# TramHanSTM8.net
KiCad netlist of a schematic drawn in Altium Designer
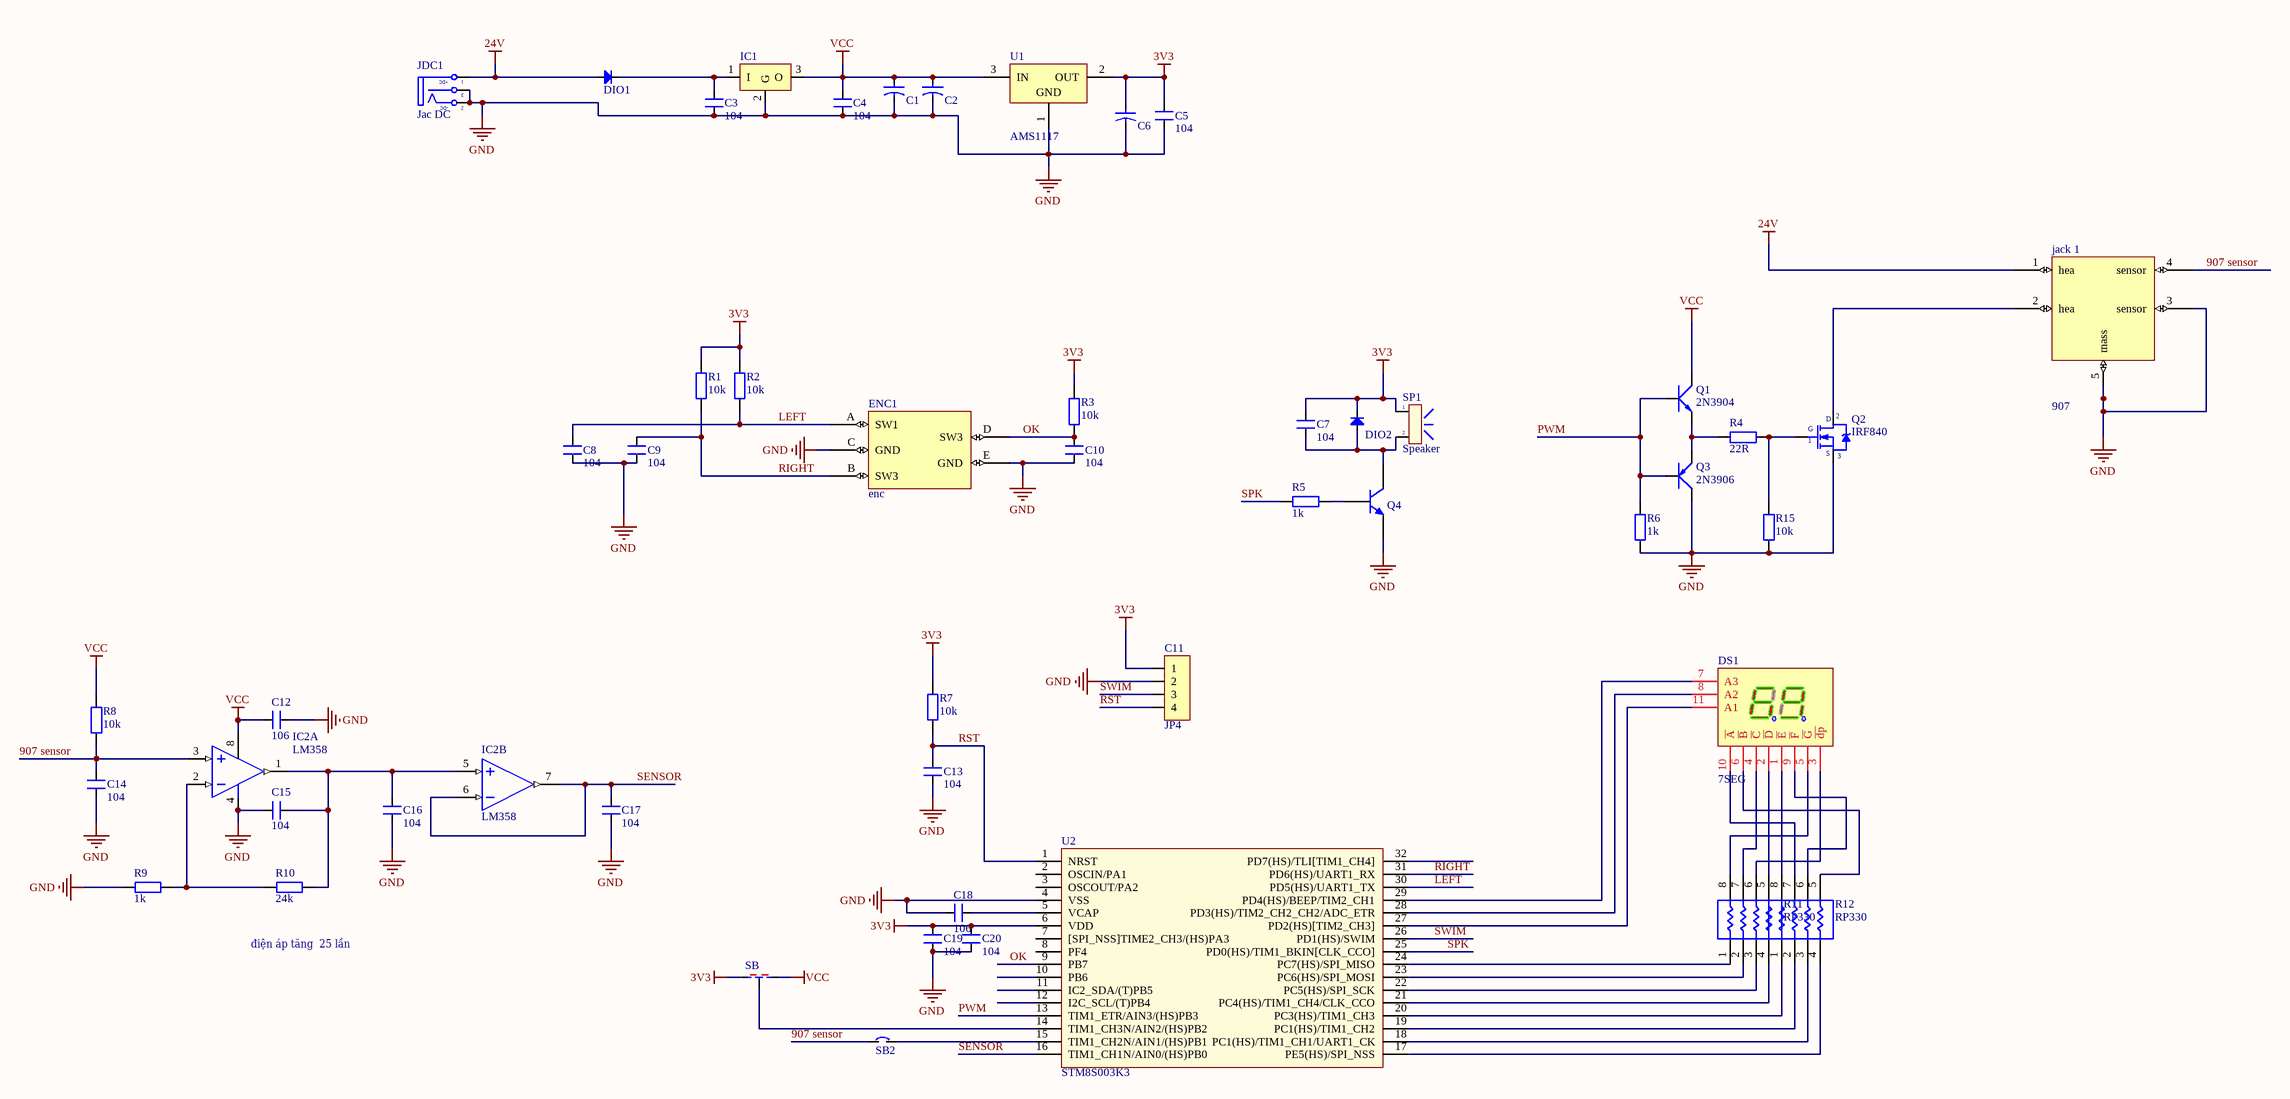
[diagram p0: TramHanSTM8.SchDoc]

(export (version "E")
  (design (tool "Eeschema 10.0.6"))
  (components
    (comp (ref "C1")
      (value "CAP")
      (footprint "C 1206")
      (libsource (lib "AltiumLibraryTieuBao (1)") (part "CAP"))
    )
    (comp (ref "C2")
      (value "CAP")
      (footprint "C 1206")
      (libsource (lib "AltiumLibraryTieuBao (1)") (part "CAP"))
    )
    (comp (ref "C3")
      (value "104")
      (footprint "SM-0805")
      (description "Cap SMD")
      (libsource (lib "Tesla_Thinh") (part "CM"))
    )
    (comp (ref "C4")
      (value "104")
      (footprint "SM-0805")
      (description "Cap SMD")
      (libsource (lib "Tesla_Thinh") (part "CM"))
    )
    (comp (ref "C5")
      (value "104")
      (footprint "SM-0805")
      (description "Cap SMD")
      (libsource (lib "Tesla_Thinh") (part "CM"))
    )
    (comp (ref "C6")
      (value "CAP")
      (footprint "C 1206")
      (libsource (lib "AltiumLibraryTieuBao (1)") (part "CAP"))
    )
    (comp (ref "C7")
      (value "104")
      (footprint "SM-0805")
      (description "Cap SMD")
      (libsource (lib "Tesla_Thinh") (part "CM"))
    )
    (comp (ref "C8")
      (value "104")
      (footprint "SM-0805")
      (description "Cap SMD")
      (libsource (lib "Tesla_Thinh") (part "CM"))
    )
    (comp (ref "C9")
      (value "104")
      (footprint "SM-0805")
      (description "Cap SMD")
      (libsource (lib "Tesla_Thinh") (part "CM"))
    )
    (comp (ref "C10")
      (value "104")
      (footprint "SM-0805")
      (description "Cap SMD")
      (libsource (lib "Tesla_Thinh") (part "CM"))
    )
    (comp (ref "C11")
      (value "JP4")
      (footprint "JP4-C1T")
      (description "WR-PHD 2.54 mm Angled Socket Header")
      (fields
        (field (name "MANUFACTURER") "Würth Elektronik eiSos GmbH")
        (field (name "PARTNO") "613004143121")
        (field (name "CREATED BY") "Karrer Zheng")
      )
      (libsource (lib "Tesla_Thinh") (part "JP4"))
    )
    (comp (ref "C12")
      (value "106")
      (footprint "SM-0805")
      (description "Cap SMD")
      (libsource (lib "Tesla_Thinh") (part "CM"))
    )
    (comp (ref "C13")
      (value "104")
      (footprint "SM-0805")
      (description "Cap SMD")
      (libsource (lib "Tesla_Thinh") (part "CM"))
    )
    (comp (ref "C14")
      (value "104")
      (footprint "SM-0805")
      (description "Cap SMD")
      (libsource (lib "Tesla_Thinh") (part "CM"))
    )
    (comp (ref "C15")
      (value "104")
      (footprint "SM-0805")
      (description "Cap SMD")
      (libsource (lib "Tesla_Thinh") (part "CM"))
    )
    (comp (ref "C16")
      (value "104")
      (footprint "SM-0805")
      (description "Cap SMD")
      (libsource (lib "Tesla_Thinh") (part "CM"))
    )
    (comp (ref "C17")
      (value "104")
      (footprint "SM-0805")
      (description "Cap SMD")
      (libsource (lib "Tesla_Thinh") (part "CM"))
    )
    (comp (ref "C18")
      (value "106")
      (footprint "SM-0805")
      (description "Cap SMD")
      (libsource (lib "Tesla_Thinh") (part "CM"))
    )
    (comp (ref "C19")
      (value "104")
      (footprint "SM-0805")
      (description "Cap SMD")
      (libsource (lib "Tesla_Thinh") (part "CM"))
    )
    (comp (ref "C20")
      (value "104")
      (footprint "SM-0805")
      (description "Cap SMD")
      (libsource (lib "Tesla_Thinh") (part "CM"))
    )
    (comp (ref "DIO1")
      (value "Diode SMD")
      (footprint "DIO-SMD-106")
      (description "Default Diode")
      (fields (field (name "PUBLISHER") "Altium Limited"))
      (libsource (lib "Tesla_Thinh") (part "Diode SMD"))
    )
    (comp (ref "DIO2")
      (value "Diode SMD")
      (footprint "DIO-SMD-106")
      (description "Default Diode")
      (fields (field (name "PUBLISHER") "Altium Limited"))
      (libsource (lib "Tesla_Thinh") (part "Diode SMD"))
    )
    (comp (ref "DS1")
      (value "7SEG")
      (footprint "LED 7 SEG 3 DIGIT")
      (libsource (lib "Tesla_Thinh") (part "LED 7 SEG 3 DIGIT"))
    )
    (comp (ref "ENC1") (value "enc") (footprint "ENC") (libsource (lib "Tesla_Thinh") (part "ENC")))
    (comp (ref "IC1")
      (value "LM7805 SOT89")
      (footprint "SOT89-321")
      (description "Positive Voltage Regulator")
      (fields (field (name "PUBLISHER") "Altium Limited"))
      (libsource (lib "Tesla_Thinh") (part "LM78xx"))
    )
    (comp (ref "IC2")
      (value "LM358")
      (footprint "SO8")
      (description "Low-Power Dual Operational Amplifier")
      (libsource (lib "Tesla_Thinh") (part "LM358"))
    )
    (comp (ref "jack 1") (value "907") (footprint "jack 907") (libsource (lib "907") (part "jack 907")))
    (comp (ref "JDC1")
      (value "Jac DC")
      (footprint "DC0")
      (description "Jac DC input")
      (libsource (lib "Tesla_Thinh") (part "DCIN"))
    )
    (comp (ref "Q1")
      (value "2N3904")
      (footprint "SOT23-231")
      (description "NPN 600mW, ECB")
      (libsource (lib "Tesla_Thinh") (part "2N904"))
    )
    (comp (ref "Q2")
      (value "IRF840")
      (footprint "TO252-123")
      (description "MOSFET N - CHANNEL 500V - 0.75 - 8A - TO-220")
      (libsource (lib "Tesla_Thinh") (part "IRF840"))
    )
    (comp (ref "Q3")
      (value "2N3906")
      (footprint "SOT23-231")
      (description "PNP 600mW, ECB")
      (libsource (lib "Tesla_Thinh") (part "2N3906"))
    )
    (comp (ref "Q4") (value "C1815") (footprint "SOT 23") (libsource (lib "Tesla_Thinh") (part "C1815_SMD")))
    (comp (ref "R1")
      (value "10k")
      (footprint "SM-RES-0805")
      (description "Resistor 1/4W")
      (libsource (lib "Tesla_Thinh") (part "R1/4W"))
    )
    (comp (ref "R2")
      (value "10k")
      (footprint "SM-RES-0805")
      (description "Resistor 1/4W")
      (libsource (lib "Tesla_Thinh") (part "R1/4W"))
    )
    (comp (ref "R3")
      (value "10k")
      (footprint "SM-RES-0805")
      (description "Resistor 1/4W")
      (libsource (lib "Tesla_Thinh") (part "R1/4W"))
    )
    (comp (ref "R4")
      (value "22R")
      (footprint "SM-RES-0805")
      (description "Resistor 1/4W")
      (libsource (lib "Tesla_Thinh") (part "R1/4W"))
    )
    (comp (ref "R5")
      (value "1k")
      (footprint "SM-RES-0805")
      (description "Resistor 1/4W")
      (libsource (lib "Tesla_Thinh") (part "R1/4W"))
    )
    (comp (ref "R6")
      (value "1k")
      (footprint "SM-RES-0805")
      (description "Resistor 1/4W")
      (libsource (lib "Tesla_Thinh") (part "R1/4W"))
    )
    (comp (ref "R7")
      (value "10k")
      (footprint "SM-RES-0805")
      (description "Resistor 1/4W")
      (libsource (lib "Tesla_Thinh") (part "R1/4W"))
    )
    (comp (ref "R8")
      (value "10k")
      (footprint "SM-RES-0805")
      (description "Resistor 1/4W")
      (libsource (lib "Tesla_Thinh") (part "R1/4W"))
    )
    (comp (ref "R9")
      (value "1k")
      (footprint "SM-RES-0805")
      (description "Resistor 1/4W")
      (libsource (lib "Tesla_Thinh") (part "R1/4W"))
    )
    (comp (ref "R10")
      (value "24k")
      (footprint "SM-RES-0805")
      (description "Resistor 1/4W")
      (libsource (lib "Tesla_Thinh") (part "R1/4W"))
    )
    (comp (ref "R11")
      (value "RP330")
      (footprint "RESCAXS50P160X320X70-8N")
      (libsource (lib "PCB_Project") (part "ResPack"))
    )
    (comp (ref "R12")
      (value "RP330")
      (footprint "RESCAXS50P160X320X70-8N")
      (libsource (lib "PCB_Project") (part "ResPack"))
    )
    (comp (ref "R15")
      (value "10k")
      (footprint "SM-RES-0805")
      (description "Resistor 1/4W")
      (libsource (lib "Tesla_Thinh") (part "R1/4W"))
    )
    (comp (ref "SB") (value "~") (footprint "SB_3") (libsource (lib "OBIT_TESLA") (part "SB_3")))
    (comp (ref "SB2") (value "SB") (footprint "SB") (libsource (lib "OBIT_TESLA") (part "SB")))
    (comp (ref "SP1")
      (value "Speaker")
      (footprint "SPEAKER")
      (description "Speaker Chip")
      (libsource (lib "Tesla_Thinh") (part "SPK"))
    )
    (comp (ref "U1") (value "AMS1117") (footprint "SOT 223") (libsource (lib "Obit_Library") (part "AMS117")))
    (comp (ref "U2")
      (value "STM8S003K3")
      (footprint "TQFP32")
      (description "MCU 8BIT  8KB FLASH LQFP-32")
      (libsource (lib "Tesla_Thinh") (part "STM8S003K3"))
    )
  )
  (nets
    (net (code "1") (name "/907 sensor") (class "Default")
      (node (ref "C14") (pin "2") (pinfunction "2_2") (pintype "passive"))
      (node (ref "IC2") (pin "3") (pinfunction "IN+_3") (pintype "input"))
      (node (ref "R8") (pin "2") (pinfunction "2_2") (pintype "passive"))
      (node (ref "SB2") (pin "1") (pintype "passive"))
      (node (ref "jack 1") (pin "4") (pinfunction "sensor_4") (pintype "bidirectional"))
    )
    (net (code "2") (name "/LEFT") (class "Default")
      (node (ref "C8") (pin "1") (pinfunction "1_1") (pintype "passive"))
      (node (ref "ENC1") (pin "A") (pinfunction "SW1_A") (pintype "bidirectional"))
      (node (ref "R2") (pin "1") (pinfunction "1_1") (pintype "passive"))
      (node (ref "U2") (pin "30") (pinfunction "PD5(HS)/UART1_TX_30") (pintype "passive"))
    )
    (net (code "3") (name "/OK") (class "Default")
      (node (ref "C10") (pin "1") (pinfunction "1_1") (pintype "passive"))
      (node (ref "ENC1") (pin "D") (pinfunction "SW3_D") (pintype "bidirectional"))
      (node (ref "R3") (pin "1") (pinfunction "1_1") (pintype "passive"))
      (node (ref "U2") (pin "9") (pinfunction "PB7_9") (pintype "passive"))
    )
    (net (code "4") (name "/PWM") (class "Default")
      (node (ref "Q1") (pin "2") (pinfunction "B_2") (pintype "passive"))
      (node (ref "Q3") (pin "2") (pinfunction "B_2") (pintype "passive"))
      (node (ref "R6") (pin "2") (pinfunction "2_2") (pintype "passive"))
      (node (ref "U2") (pin "13") (pinfunction "TIM1_ETR/AIN3/(HS)PB3_13") (pintype "passive"))
    )
    (net (code "5") (name "/RIGHT") (class "Default")
      (node (ref "C9") (pin "1") (pinfunction "1_1") (pintype "passive"))
      (node (ref "ENC1") (pin "B") (pinfunction "SW3_B") (pintype "bidirectional"))
      (node (ref "R1") (pin "1") (pinfunction "1_1") (pintype "passive"))
      (node (ref "U2") (pin "31") (pinfunction "PD6(HS)/UART1_RX_31") (pintype "passive"))
    )
    (net (code "6") (name "/RST") (class "Default")
      (node (ref "C11") (pin "4") (pinfunction "4_4") (pintype "passive"))
      (node (ref "C13") (pin "2") (pinfunction "2_2") (pintype "passive"))
      (node (ref "R7") (pin "2") (pinfunction "2_2") (pintype "passive"))
      (node (ref "U2") (pin "1") (pinfunction "NRST_1") (pintype "passive"))
    )
    (net (code "7") (name "/SENSOR") (class "Default")
      (node (ref "C17") (pin "1") (pinfunction "1_1") (pintype "passive"))
      (node (ref "IC2") (pin "6") (pinfunction "IN-_6") (pintype "input"))
      (node (ref "IC2") (pin "7") (pinfunction "OUT_7") (pintype "output"))
      (node (ref "U2") (pin "16") (pinfunction "TIM1_CH1N/AIN0/(HS)PB0_16") (pintype "passive"))
    )
    (net (code "8") (name "/SPK") (class "Default")
      (node (ref "R5") (pin "1") (pinfunction "1_1") (pintype "passive"))
      (node (ref "U2") (pin "25") (pinfunction "PD0(HS)/TIM1_BKIN[CLK_CCO]_25") (pintype "passive"))
    )
    (net (code "9") (name "/SWIM") (class "Default")
      (node (ref "C11") (pin "3") (pinfunction "3_3") (pintype "passive"))
      (node (ref "U2") (pin "26") (pinfunction "PD1(HS)/SWIM_26") (pintype "passive"))
    )
    (net (code "10") (name "3V3") (class "Default")
      (node (ref "C11") (pin "1") (pinfunction "1_1") (pintype "passive"))
      (node (ref "C19") (pin "1") (pinfunction "1_1") (pintype "passive"))
      (node (ref "C20") (pin "1") (pinfunction "1_1") (pintype "passive"))
      (node (ref "C5") (pin "2") (pinfunction "2_2") (pintype "passive"))
      (node (ref "C6") (pin "1") (pinfunction "1_1") (pintype "passive"))
      (node (ref "C7") (pin "1") (pinfunction "1_1") (pintype "passive"))
      (node (ref "DIO2") (pin "2") (pinfunction "K_2") (pintype "passive"))
      (node (ref "R1") (pin "2") (pinfunction "2_2") (pintype "passive"))
      (node (ref "R2") (pin "2") (pinfunction "2_2") (pintype "passive"))
      (node (ref "R3") (pin "2") (pinfunction "2_2") (pintype "passive"))
      (node (ref "R7") (pin "1") (pinfunction "1_1") (pintype "passive"))
      (node (ref "SB") (pin "1") (pinfunction "1_1") (pintype "passive"))
      (node (ref "SP1") (pin "1") (pinfunction "1_1") (pintype "passive"))
      (node (ref "U1") (pin "2") (pinfunction "OUT_2") (pintype "power_in"))
      (node (ref "U2") (pin "6") (pinfunction "VDD_6") (pintype "passive"))
    )
    (net (code "11") (name "24V") (class "Default")
      (node (ref "DIO1") (pin "1") (pinfunction "A_1") (pintype "passive"))
      (node (ref "JDC1") (pin "1") (pinfunction "T_1") (pintype "passive"))
      (node (ref "jack 1") (pin "1") (pinfunction "hea_1") (pintype "bidirectional"))
    )
    (net (code "12") (name "GND") (class "Default")
      (node (ref "C1") (pin "2") (pinfunction "2_2") (pintype "passive"))
      (node (ref "C10") (pin "2") (pinfunction "2_2") (pintype "passive"))
      (node (ref "C11") (pin "2") (pinfunction "2_2") (pintype "passive"))
      (node (ref "C12") (pin "1") (pinfunction "1_1") (pintype "passive"))
      (node (ref "C13") (pin "1") (pinfunction "1_1") (pintype "passive"))
      (node (ref "C14") (pin "1") (pinfunction "1_1") (pintype "passive"))
      (node (ref "C15") (pin "2") (pinfunction "2_2") (pintype "passive"))
      (node (ref "C16") (pin "2") (pinfunction "2_2") (pintype "passive"))
      (node (ref "C17") (pin "2") (pinfunction "2_2") (pintype "passive"))
      (node (ref "C18") (pin "2") (pinfunction "2_2") (pintype "passive"))
      (node (ref "C19") (pin "2") (pinfunction "2_2") (pintype "passive"))
      (node (ref "C2") (pin "2") (pinfunction "2_2") (pintype "passive"))
      (node (ref "C20") (pin "2") (pinfunction "2_2") (pintype "passive"))
      (node (ref "C3") (pin "1") (pinfunction "1_1") (pintype "passive"))
      (node (ref "C4") (pin "1") (pinfunction "1_1") (pintype "passive"))
      (node (ref "C5") (pin "1") (pinfunction "1_1") (pintype "passive"))
      (node (ref "C6") (pin "2") (pinfunction "2_2") (pintype "passive"))
      (node (ref "C8") (pin "2") (pinfunction "2_2") (pintype "passive"))
      (node (ref "C9") (pin "2") (pinfunction "2_2") (pintype "passive"))
      (node (ref "ENC1") (pin "C") (pinfunction "GND_C") (pintype "bidirectional"))
      (node (ref "ENC1") (pin "E") (pinfunction "GND_E") (pintype "bidirectional"))
      (node (ref "IC1") (pin "2") (pinfunction "G_2") (pintype "power_in"))
      (node (ref "IC2") (pin "4") (pinfunction "-V_4") (pintype "passive"))
      (node (ref "JDC1") (pin "2") (pinfunction "TN_2") (pintype "passive"))
      (node (ref "JDC1") (pin "3") (pinfunction "S_3") (pintype "power_in"))
      (node (ref "Q2") (pin "3") (pinfunction "S_3") (pintype "passive"))
      (node (ref "Q3") (pin "3") (pinfunction "C_3") (pintype "passive"))
      (node (ref "Q4") (pin "2") (pinfunction "E_2") (pintype "passive"))
      (node (ref "R15") (pin "1") (pinfunction "1_1") (pintype "passive"))
      (node (ref "R6") (pin "1") (pinfunction "1_1") (pintype "passive"))
      (node (ref "R9") (pin "2") (pinfunction "2_2") (pintype "passive"))
      (node (ref "U1") (pin "1") (pinfunction "GND_1") (pintype "power_in"))
      (node (ref "U2") (pin "4") (pinfunction "VSS_4") (pintype "passive"))
      (node (ref "jack 1") (pin "3") (pinfunction "sensor_3") (pintype "bidirectional"))
      (node (ref "jack 1") (pin "5") (pinfunction "mass_5") (pintype "bidirectional"))
    )
    (net (code "13") (name "Net-(DIO1-K)") (class "Default")
      (node (ref "C3") (pin "2") (pinfunction "2_2") (pintype "passive"))
      (node (ref "DIO1") (pin "2") (pinfunction "K_2") (pintype "passive"))
      (node (ref "IC1") (pin "1") (pinfunction "I_1") (pintype "power_in"))
    )
    (net (code "14") (name "Net-(DIO2-A)") (class "Default")
      (node (ref "C7") (pin "2") (pinfunction "2_2") (pintype "passive"))
      (node (ref "DIO2") (pin "1") (pinfunction "A_1") (pintype "passive"))
      (node (ref "Q4") (pin "3") (pinfunction "C_3") (pintype "passive"))
      (node (ref "SP1") (pin "2") (pinfunction "2_2") (pintype "passive"))
    )
    (net (code "15") (name "Net-(DS1-A1)") (class "Default")
      (node (ref "DS1") (pin "11") (pinfunction "A1_11") (pintype "passive"))
      (node (ref "U2") (pin "27") (pinfunction "PD2(HS)[TIM2_CH3]_27") (pintype "passive"))
    )
    (net (code "16") (name "Net-(DS1-A2)") (class "Default")
      (node (ref "DS1") (pin "8") (pinfunction "A2_8") (pintype "passive"))
      (node (ref "U2") (pin "28") (pinfunction "PD3(HS)/TIM2_CH2_CH2/ADC_ETR_28") (pintype "passive"))
    )
    (net (code "17") (name "Net-(DS1-A3)") (class "Default")
      (node (ref "DS1") (pin "7") (pinfunction "A3_7") (pintype "passive"))
      (node (ref "U2") (pin "29") (pinfunction "PD4(HS)/BEEP/TIM2_CH1_29") (pintype "passive"))
    )
    (net (code "18") (name "Net-(DS1-~{A})") (class "Default")
      (node (ref "DS1") (pin "10") (pinfunction "~{A}_10") (pintype "passive"))
      (node (ref "R12") (pin "7") (pinfunction "7_7") (pintype "passive"))
    )
    (net (code "19") (name "Net-(DS1-~{B})") (class "Default")
      (node (ref "DS1") (pin "6") (pinfunction "~{B}_6") (pintype "passive"))
      (node (ref "R12") (pin "5") (pinfunction "5_5") (pintype "passive"))
    )
    (net (code "20") (name "Net-(DS1-~{C})") (class "Default")
      (node (ref "DS1") (pin "4") (pinfunction "~{C}_4") (pintype "passive"))
      (node (ref "R11") (pin "7") (pinfunction "7_7") (pintype "passive"))
    )
    (net (code "21") (name "Net-(DS1-~{D})") (class "Default")
      (node (ref "DS1") (pin "2") (pinfunction "~{D}_2") (pintype "passive"))
      (node (ref "R11") (pin "5") (pinfunction "5_5") (pintype "passive"))
    )
    (net (code "22") (name "Net-(DS1-~{E})") (class "Default")
      (node (ref "DS1") (pin "1") (pinfunction "~{E}_1") (pintype "passive"))
      (node (ref "R12") (pin "8") (pinfunction "8_8") (pintype "passive"))
    )
    (net (code "23") (name "Net-(DS1-~{F})") (class "Default")
      (node (ref "DS1") (pin "9") (pinfunction "~{F}_9") (pintype "passive"))
      (node (ref "R12") (pin "6") (pinfunction "6_6") (pintype "passive"))
    )
    (net (code "24") (name "Net-(DS1-~{G})") (class "Default")
      (node (ref "DS1") (pin "5") (pinfunction "~{G}_5") (pintype "passive"))
      (node (ref "R11") (pin "8") (pinfunction "8_8") (pintype "passive"))
    )
    (net (code "25") (name "Net-(DS1-~{dp})") (class "Default")
      (node (ref "DS1") (pin "3") (pinfunction "~{dp}_3") (pintype "passive"))
      (node (ref "R11") (pin "6") (pinfunction "6_6") (pintype "passive"))
    )
    (net (code "26") (name "Net-(IC2A-IN-)") (class "Default")
      (node (ref "IC2") (pin "2") (pinfunction "IN-_2") (pintype "input"))
      (node (ref "R10") (pin "2") (pinfunction "2_2") (pintype "passive"))
      (node (ref "R9") (pin "1") (pinfunction "1_1") (pintype "passive"))
    )
    (net (code "27") (name "Net-(IC2A-OUT)") (class "Default")
      (node (ref "C15") (pin "1") (pinfunction "1_1") (pintype "passive"))
      (node (ref "C16") (pin "1") (pinfunction "1_1") (pintype "passive"))
      (node (ref "IC2") (pin "1") (pinfunction "OUT_1") (pintype "output"))
      (node (ref "IC2") (pin "5") (pinfunction "IN+_5") (pintype "input"))
      (node (ref "R10") (pin "1") (pinfunction "1_1") (pintype "passive"))
    )
    (net (code "28") (name "Net-(Q1-E)") (class "Default")
      (node (ref "Q1") (pin "1") (pinfunction "E_1") (pintype "passive"))
      (node (ref "Q3") (pin "1") (pinfunction "E_1") (pintype "passive"))
      (node (ref "R4") (pin "2") (pinfunction "2_2") (pintype "passive"))
    )
    (net (code "29") (name "Net-(Q2-D)") (class "Default")
      (node (ref "Q2") (pin "2") (pinfunction "D_2") (pintype "passive"))
      (node (ref "jack 1") (pin "2") (pinfunction "hea_2") (pintype "bidirectional"))
    )
    (net (code "30") (name "Net-(Q2-G)") (class "Default")
      (node (ref "Q2") (pin "1") (pinfunction "G_1") (pintype "passive"))
      (node (ref "R15") (pin "2") (pinfunction "2_2") (pintype "passive"))
      (node (ref "R4") (pin "1") (pinfunction "1_1") (pintype "passive"))
    )
    (net (code "31") (name "Net-(Q4-B)") (class "Default")
      (node (ref "Q4") (pin "1") (pinfunction "B_1") (pintype "passive"))
      (node (ref "R5") (pin "2") (pinfunction "2_2") (pintype "passive"))
    )
    (net (code "32") (name "Net-(U2-PC1(HS){slash}TIM1_CH1{slash}UART1_CK)") (class "Default")
      (node (ref "R12") (pin "3") (pinfunction "3_3") (pintype "passive"))
      (node (ref "U2") (pin "18") (pinfunction "PC1(HS)/TIM1_CH1/UART1_CK_18") (pintype "passive"))
    )
    (net (code "33") (name "Net-(U2-PC1(HS){slash}TIM1_CH2)") (class "Default")
      (node (ref "R12") (pin "2") (pinfunction "2_2") (pintype "passive"))
      (node (ref "U2") (pin "19") (pinfunction "PC1(HS)/TIM1_CH2_19") (pintype "passive"))
    )
    (net (code "34") (name "Net-(U2-PC3(HS){slash}TIM1_CH3)") (class "Default")
      (node (ref "R12") (pin "1") (pinfunction "1_1") (pintype "passive"))
      (node (ref "U2") (pin "20") (pinfunction "PC3(HS)/TIM1_CH3_20") (pintype "passive"))
    )
    (net (code "35") (name "Net-(U2-PC4(HS){slash}TIM1_CH4{slash}CLK_CCO)") (class "Default")
      (node (ref "R11") (pin "4") (pinfunction "4_4") (pintype "passive"))
      (node (ref "U2") (pin "21") (pinfunction "PC4(HS)/TIM1_CH4/CLK_CCO_21") (pintype "passive"))
    )
    (net (code "36") (name "Net-(U2-PC5(HS){slash}SPI_SCK)") (class "Default")
      (node (ref "R11") (pin "3") (pinfunction "3_3") (pintype "passive"))
      (node (ref "U2") (pin "22") (pinfunction "PC5(HS)/SPI_SCK_22") (pintype "passive"))
    )
    (net (code "37") (name "Net-(U2-PC6(HS){slash}SPI_MOSI)") (class "Default")
      (node (ref "R11") (pin "2") (pinfunction "2_2") (pintype "passive"))
      (node (ref "U2") (pin "23") (pinfunction "PC6(HS)/SPI_MOSI_23") (pintype "passive"))
    )
    (net (code "38") (name "Net-(U2-PC7(HS){slash}SPI_MISO)") (class "Default")
      (node (ref "R11") (pin "1") (pinfunction "1_1") (pintype "passive"))
      (node (ref "U2") (pin "24") (pinfunction "PC7(HS)/SPI_MISO_24") (pintype "passive"))
    )
    (net (code "39") (name "Net-(U2-PE5(HS){slash}SPI_NSS)") (class "Default")
      (node (ref "R12") (pin "4") (pinfunction "4_4") (pintype "passive"))
      (node (ref "U2") (pin "17") (pinfunction "PE5(HS)/SPI_NSS_17") (pintype "passive"))
    )
    (net (code "40") (name "Net-(U2-TIM1_CH2N{slash}AIN1{slash}(HS)PB1)") (class "Default")
      (node (ref "SB2") (pin "2") (pintype "passive"))
      (node (ref "U2") (pin "15") (pinfunction "TIM1_CH2N/AIN1/(HS)PB1_15") (pintype "passive"))
    )
    (net (code "41") (name "Net-(U2-TIM1_CH3N{slash}AIN2{slash}(HS)PB2)") (class "Default")
      (node (ref "SB") (pin "2") (pinfunction "2_2") (pintype "passive"))
      (node (ref "U2") (pin "14") (pinfunction "TIM1_CH3N/AIN2/(HS)PB2_14") (pintype "passive"))
    )
    (net (code "42") (name "Net-(U2-VCAP)") (class "Default")
      (node (ref "C18") (pin "1") (pinfunction "1_1") (pintype "passive"))
      (node (ref "U2") (pin "5") (pinfunction "VCAP_5") (pintype "passive"))
    )
    (net (code "43") (name "VCC") (class "Default")
      (node (ref "C1") (pin "1") (pinfunction "1_1") (pintype "passive"))
      (node (ref "C12") (pin "2") (pinfunction "2_2") (pintype "passive"))
      (node (ref "C2") (pin "1") (pinfunction "1_1") (pintype "passive"))
      (node (ref "C4") (pin "2") (pinfunction "2_2") (pintype "passive"))
      (node (ref "IC1") (pin "3") (pinfunction "O_3") (pintype "power_in"))
      (node (ref "IC2") (pin "8") (pinfunction "+V_8") (pintype "passive"))
      (node (ref "Q1") (pin "3") (pinfunction "C_3") (pintype "passive"))
      (node (ref "R8") (pin "1") (pinfunction "1_1") (pintype "passive"))
      (node (ref "SB") (pin "3") (pinfunction "3_3") (pintype "passive"))
      (node (ref "U1") (pin "3") (pinfunction "IN_3") (pintype "power_in"))
    )
    (net (code "44") (name "unconnected-(U2-I2C_SCL{slash}(T)PB4-Pad12)") (class "Default")
      (node (ref "U2") (pin "12") (pinfunction "I2C_SCL/(T)PB4_12") (pintype "passive"))
    )
    (net (code "45") (name "unconnected-(U2-IC2_SDA{slash}(T)PB5-Pad11)") (class "Default")
      (node (ref "U2") (pin "11") (pinfunction "IC2_SDA/(T)PB5_11") (pintype "passive"))
    )
    (net (code "46") (name "unconnected-(U2-OSCIN{slash}PA1-Pad2)") (class "Default")
      (node (ref "U2") (pin "2") (pinfunction "OSCIN/PA1_2") (pintype "passive"))
    )
    (net (code "47") (name "unconnected-(U2-OSCOUT{slash}PA2-Pad3)") (class "Default")
      (node (ref "U2") (pin "3") (pinfunction "OSCOUT/PA2_3") (pintype "passive"))
    )
    (net (code "48") (name "unconnected-(U2-PB6-Pad10)") (class "Default")
      (node (ref "U2") (pin "10") (pinfunction "PB6_10") (pintype "passive"))
    )
    (net (code "49") (name "unconnected-(U2-PD7(HS){slash}TLI[TIM1_CH4]-Pad32)") (class "Default")
      (node (ref "U2") (pin "32") (pinfunction "PD7(HS)/TLI[TIM1_CH4]_32") (pintype "passive"))
    )
    (net (code "50") (name "unconnected-(U2-PF4-Pad8)") (class "Default")
      (node (ref "U2") (pin "8") (pinfunction "PF4_8") (pintype "passive"))
    )
    (net (code "51") (name "unconnected-(U2-[SPI_NSS]TIME2_CH3{slash}(HS)PA3-Pad7)") (class "Default")
      (node (ref "U2") (pin "7") (pinfunction "[SPI_NSS]TIME2_CH3/(HS)PA3_7") (pintype "passive"))
    )
  )
)
